# REZZ-Style_goggles.net
KiCad netlist of a schematic drawn in EAGLE
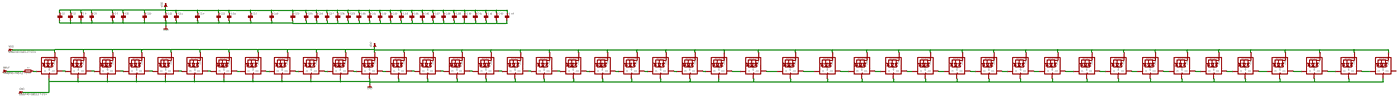
[diagram p0: schematic, sheet 1, overview]
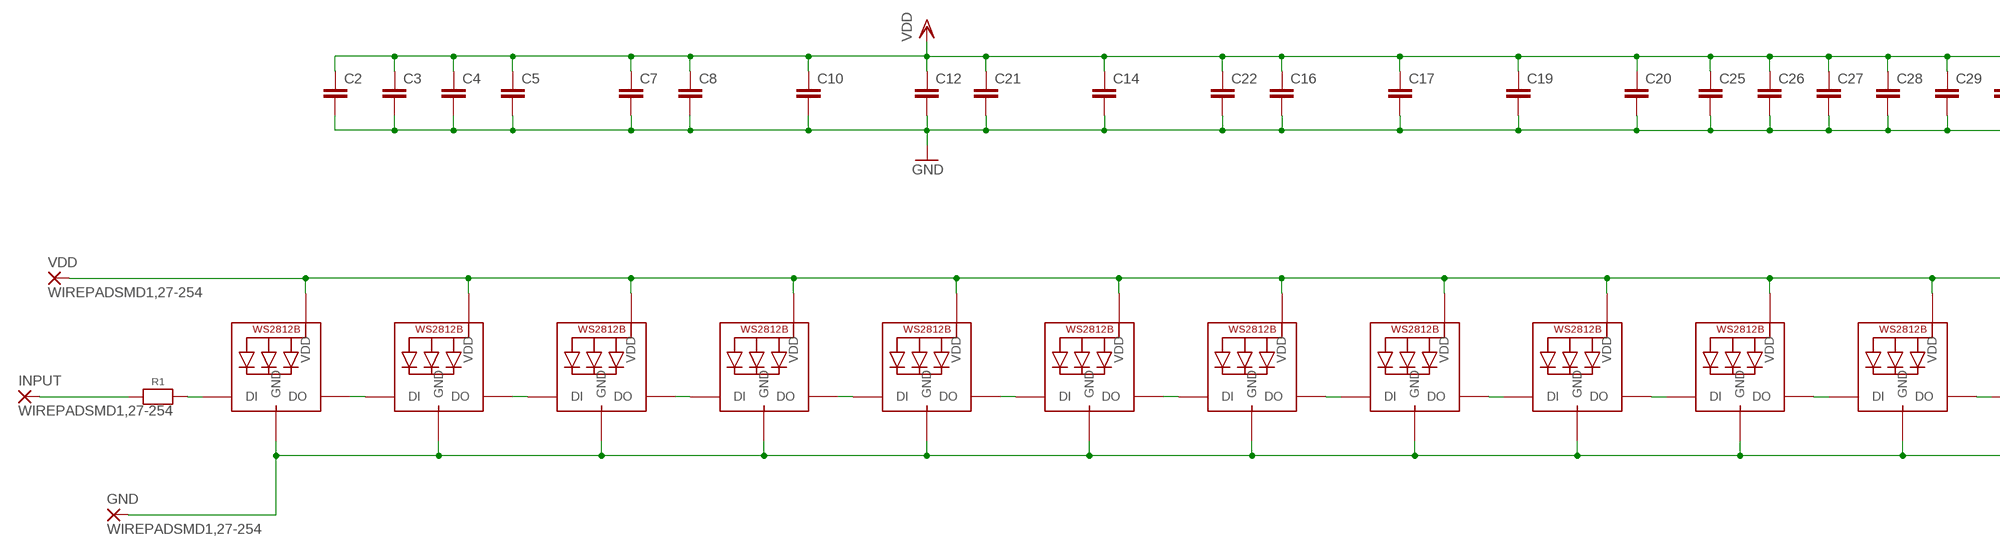
[diagram p1: schematic, sheet 1, part 1 of 4]
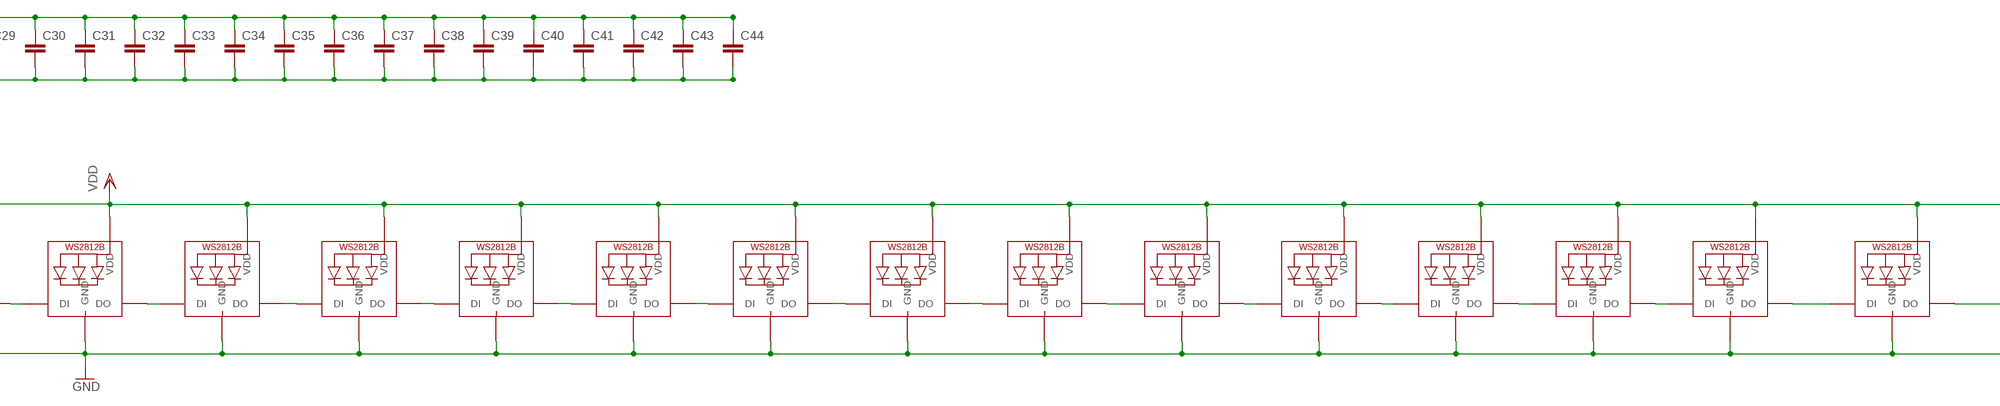
[diagram p2: schematic, sheet 1, part 2 of 4]
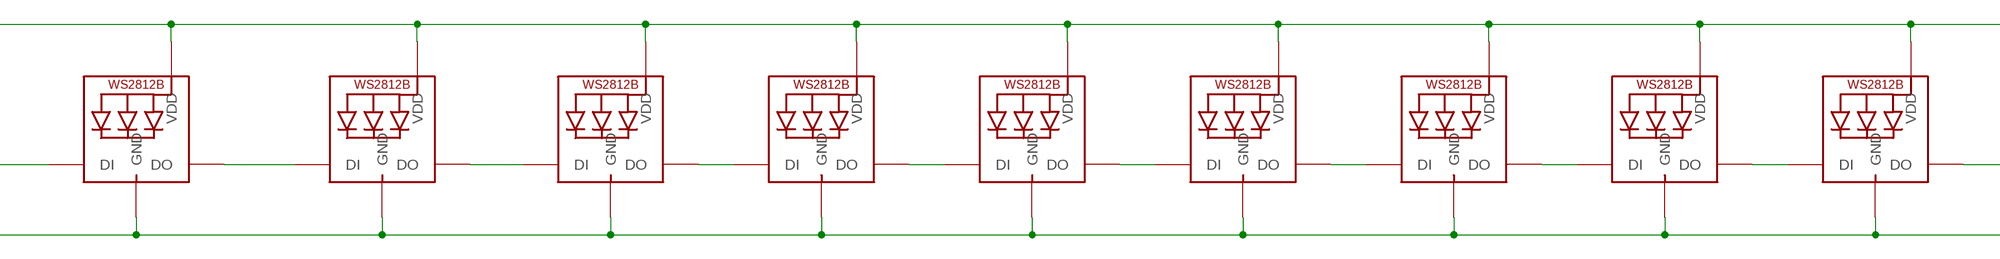
[diagram p3: schematic, sheet 1, part 3 of 4]
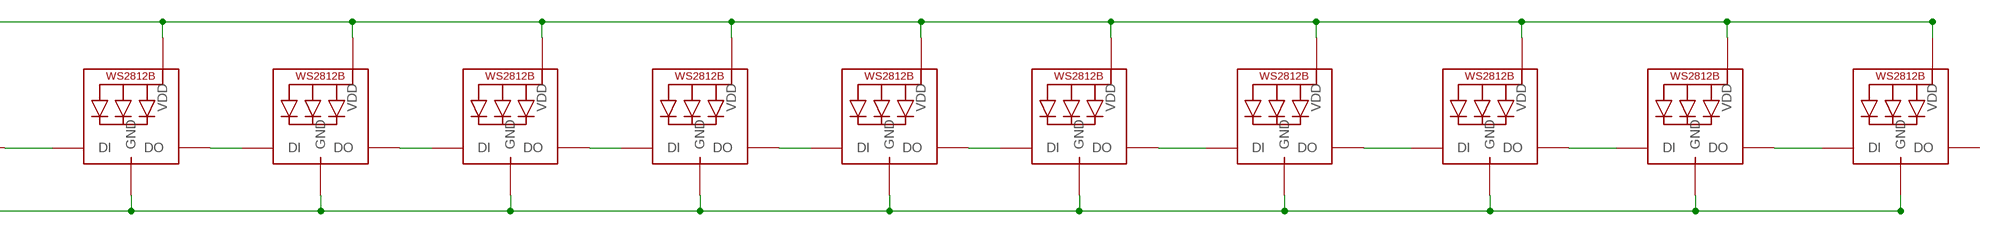
[diagram p4: schematic, sheet 1, part 4 of 4]

(export (version "E")
  (design (tool "Eeschema 10.0.6"))
  (components
    (comp (ref "C2")
      (value "C-EUC0603")
      (footprint "eagle-import:C0603")
      (libsource (lib "eagle-import") (part "C-EUC0603"))
    )
    (comp (ref "C3")
      (value "C-EUC0603")
      (footprint "eagle-import:C0603")
      (libsource (lib "eagle-import") (part "C-EUC0603"))
    )
    (comp (ref "C4")
      (value "C-EUC0603")
      (footprint "eagle-import:C0603")
      (libsource (lib "eagle-import") (part "C-EUC0603"))
    )
    (comp (ref "C5")
      (value "C-EUC0603")
      (footprint "eagle-import:C0603")
      (libsource (lib "eagle-import") (part "C-EUC0603"))
    )
    (comp (ref "C7")
      (value "C-EUC0603")
      (footprint "eagle-import:C0603")
      (libsource (lib "eagle-import") (part "C-EUC0603"))
    )
    (comp (ref "C8")
      (value "C-EUC0603")
      (footprint "eagle-import:C0603")
      (libsource (lib "eagle-import") (part "C-EUC0603"))
    )
    (comp (ref "C10")
      (value "C-EUC0603")
      (footprint "eagle-import:C0603")
      (libsource (lib "eagle-import") (part "C-EUC0603"))
    )
    (comp (ref "C12")
      (value "C-EUC0603")
      (footprint "eagle-import:C0603")
      (libsource (lib "eagle-import") (part "C-EUC0603"))
    )
    (comp (ref "C14")
      (value "C-EUC0603")
      (footprint "eagle-import:C0603")
      (libsource (lib "eagle-import") (part "C-EUC0603"))
    )
    (comp (ref "C16")
      (value "C-EUC0603")
      (footprint "eagle-import:C0603")
      (libsource (lib "eagle-import") (part "C-EUC0603"))
    )
    (comp (ref "C17")
      (value "C-EUC0603")
      (footprint "eagle-import:C0603")
      (libsource (lib "eagle-import") (part "C-EUC0603"))
    )
    (comp (ref "C19")
      (value "C-EUC0603")
      (footprint "eagle-import:C0603")
      (libsource (lib "eagle-import") (part "C-EUC0603"))
    )
    (comp (ref "C20")
      (value "C-EUC0603")
      (footprint "eagle-import:C0603")
      (libsource (lib "eagle-import") (part "C-EUC0603"))
    )
    (comp (ref "C21")
      (value "C-EUC0603")
      (footprint "eagle-import:C0603")
      (libsource (lib "eagle-import") (part "C-EUC0603"))
    )
    (comp (ref "C22")
      (value "C-EUC0603")
      (footprint "eagle-import:C0603")
      (libsource (lib "eagle-import") (part "C-EUC0603"))
    )
    (comp (ref "C25")
      (value "C-EUC0603")
      (footprint "eagle-import:C0603")
      (libsource (lib "eagle-import") (part "C-EUC0603"))
    )
    (comp (ref "C26")
      (value "C-EUC0603")
      (footprint "eagle-import:C0603")
      (libsource (lib "eagle-import") (part "C-EUC0603"))
    )
    (comp (ref "C27")
      (value "C-EUC0603")
      (footprint "eagle-import:C0603")
      (libsource (lib "eagle-import") (part "C-EUC0603"))
    )
    (comp (ref "C28")
      (value "C-EUC0603")
      (footprint "eagle-import:C0603")
      (libsource (lib "eagle-import") (part "C-EUC0603"))
    )
    (comp (ref "C29")
      (value "C-EUC0603")
      (footprint "eagle-import:C0603")
      (libsource (lib "eagle-import") (part "C-EUC0603"))
    )
    (comp (ref "C30")
      (value "C-EUC0603")
      (footprint "eagle-import:C0603")
      (libsource (lib "eagle-import") (part "C-EUC0603"))
    )
    (comp (ref "C31")
      (value "C-EUC0603")
      (footprint "eagle-import:C0603")
      (libsource (lib "eagle-import") (part "C-EUC0603"))
    )
    (comp (ref "C32")
      (value "C-EUC0603")
      (footprint "eagle-import:C0603")
      (libsource (lib "eagle-import") (part "C-EUC0603"))
    )
    (comp (ref "C33")
      (value "C-EUC0603")
      (footprint "eagle-import:C0603")
      (libsource (lib "eagle-import") (part "C-EUC0603"))
    )
    (comp (ref "C34")
      (value "C-EUC0603")
      (footprint "eagle-import:C0603")
      (libsource (lib "eagle-import") (part "C-EUC0603"))
    )
    (comp (ref "C35")
      (value "C-EUC0603")
      (footprint "eagle-import:C0603")
      (libsource (lib "eagle-import") (part "C-EUC0603"))
    )
    (comp (ref "C36")
      (value "C-EUC0603")
      (footprint "eagle-import:C0603")
      (libsource (lib "eagle-import") (part "C-EUC0603"))
    )
    (comp (ref "C37")
      (value "C-EUC0603")
      (footprint "eagle-import:C0603")
      (libsource (lib "eagle-import") (part "C-EUC0603"))
    )
    (comp (ref "C38")
      (value "C-EUC0603")
      (footprint "eagle-import:C0603")
      (libsource (lib "eagle-import") (part "C-EUC0603"))
    )
    (comp (ref "C39")
      (value "C-EUC0603")
      (footprint "eagle-import:C0603")
      (libsource (lib "eagle-import") (part "C-EUC0603"))
    )
    (comp (ref "C40")
      (value "C-EUC0603")
      (footprint "eagle-import:C0603")
      (libsource (lib "eagle-import") (part "C-EUC0603"))
    )
    (comp (ref "C41")
      (value "C-EUC0603")
      (footprint "eagle-import:C0603")
      (libsource (lib "eagle-import") (part "C-EUC0603"))
    )
    (comp (ref "C42")
      (value "C-EUC0603")
      (footprint "eagle-import:C0603")
      (libsource (lib "eagle-import") (part "C-EUC0603"))
    )
    (comp (ref "C43")
      (value "C-EUC0603")
      (footprint "eagle-import:C0603")
      (libsource (lib "eagle-import") (part "C-EUC0603"))
    )
    (comp (ref "C44")
      (value "C-EUC0603")
      (footprint "eagle-import:C0603")
      (libsource (lib "eagle-import") (part "C-EUC0603"))
    )
    (comp (ref "GND")
      (value "WIREPADSMD1,27-254")
      (footprint "eagle-import:SMD1,27-2,54")
      (libsource (lib "eagle-import") (part "WIREPADSMD1,27-254"))
    )
    (comp (ref "INPUT")
      (value "WIREPADSMD1,27-254")
      (footprint "eagle-import:SMD1,27-2,54")
      (libsource (lib "eagle-import") (part "WIREPADSMD1,27-254"))
    )
    (comp (ref "LED1")
      (value "WS2812B3535")
      (footprint "eagle-import:LED3535")
      (libsource (lib "eagle-import") (part "WS2812B3535"))
    )
    (comp (ref "LED2")
      (value "WS2812B3535")
      (footprint "eagle-import:LED3535")
      (libsource (lib "eagle-import") (part "WS2812B3535"))
    )
    (comp (ref "LED3")
      (value "WS2812B3535")
      (footprint "eagle-import:LED3535")
      (libsource (lib "eagle-import") (part "WS2812B3535"))
    )
    (comp (ref "LED4")
      (value "WS2812B3535")
      (footprint "eagle-import:LED3535")
      (libsource (lib "eagle-import") (part "WS2812B3535"))
    )
    (comp (ref "LED5")
      (value "WS2812B3535")
      (footprint "eagle-import:LED3535")
      (libsource (lib "eagle-import") (part "WS2812B3535"))
    )
    (comp (ref "LED6")
      (value "WS2812B3535")
      (footprint "eagle-import:LED3535")
      (libsource (lib "eagle-import") (part "WS2812B3535"))
    )
    (comp (ref "LED7")
      (value "WS2812B3535")
      (footprint "eagle-import:LED3535")
      (libsource (lib "eagle-import") (part "WS2812B3535"))
    )
    (comp (ref "LED8")
      (value "WS2812B3535")
      (footprint "eagle-import:LED3535")
      (libsource (lib "eagle-import") (part "WS2812B3535"))
    )
    (comp (ref "LED9")
      (value "WS2812B3535")
      (footprint "eagle-import:LED3535")
      (libsource (lib "eagle-import") (part "WS2812B3535"))
    )
    (comp (ref "LED10")
      (value "WS2812B3535")
      (footprint "eagle-import:LED3535")
      (libsource (lib "eagle-import") (part "WS2812B3535"))
    )
    (comp (ref "LED11")
      (value "WS2812B3535")
      (footprint "eagle-import:LED3535")
      (libsource (lib "eagle-import") (part "WS2812B3535"))
    )
    (comp (ref "LED12")
      (value "WS2812B3535")
      (footprint "eagle-import:LED3535")
      (libsource (lib "eagle-import") (part "WS2812B3535"))
    )
    (comp (ref "LED13")
      (value "WS2812B3535")
      (footprint "eagle-import:LED3535")
      (libsource (lib "eagle-import") (part "WS2812B3535"))
    )
    (comp (ref "LED14")
      (value "WS2812B3535")
      (footprint "eagle-import:LED3535")
      (libsource (lib "eagle-import") (part "WS2812B3535"))
    )
    (comp (ref "LED15")
      (value "WS2812B3535")
      (footprint "eagle-import:LED3535")
      (libsource (lib "eagle-import") (part "WS2812B3535"))
    )
    (comp (ref "LED16")
      (value "WS2812B3535")
      (footprint "eagle-import:LED3535")
      (libsource (lib "eagle-import") (part "WS2812B3535"))
    )
    (comp (ref "LED17")
      (value "WS2812B3535")
      (footprint "eagle-import:LED3535")
      (libsource (lib "eagle-import") (part "WS2812B3535"))
    )
    (comp (ref "LED18")
      (value "WS2812B3535")
      (footprint "eagle-import:LED3535")
      (libsource (lib "eagle-import") (part "WS2812B3535"))
    )
    (comp (ref "LED19")
      (value "WS2812B3535")
      (footprint "eagle-import:LED3535")
      (libsource (lib "eagle-import") (part "WS2812B3535"))
    )
    (comp (ref "LED20")
      (value "WS2812B3535")
      (footprint "eagle-import:LED3535")
      (libsource (lib "eagle-import") (part "WS2812B3535"))
    )
    (comp (ref "LED21")
      (value "WS2812B3535")
      (footprint "eagle-import:LED3535")
      (libsource (lib "eagle-import") (part "WS2812B3535"))
    )
    (comp (ref "LED22")
      (value "WS2812B3535")
      (footprint "eagle-import:LED3535")
      (libsource (lib "eagle-import") (part "WS2812B3535"))
    )
    (comp (ref "LED23")
      (value "WS2812B3535")
      (footprint "eagle-import:LED3535")
      (libsource (lib "eagle-import") (part "WS2812B3535"))
    )
    (comp (ref "LED24")
      (value "WS2812B3535")
      (footprint "eagle-import:LED3535")
      (libsource (lib "eagle-import") (part "WS2812B3535"))
    )
    (comp (ref "LED25")
      (value "WS2812B3535")
      (footprint "eagle-import:LED3535")
      (libsource (lib "eagle-import") (part "WS2812B3535"))
    )
    (comp (ref "LED26")
      (value "WS2812B3535")
      (footprint "eagle-import:LED3535")
      (libsource (lib "eagle-import") (part "WS2812B3535"))
    )
    (comp (ref "LED27")
      (value "WS2812B3535")
      (footprint "eagle-import:LED3535")
      (libsource (lib "eagle-import") (part "WS2812B3535"))
    )
    (comp (ref "LED28")
      (value "WS2812B3535")
      (footprint "eagle-import:LED3535")
      (libsource (lib "eagle-import") (part "WS2812B3535"))
    )
    (comp (ref "LED29")
      (value "WS2812B3535")
      (footprint "eagle-import:LED3535")
      (libsource (lib "eagle-import") (part "WS2812B3535"))
    )
    (comp (ref "LED30")
      (value "WS2812B3535")
      (footprint "eagle-import:LED3535")
      (libsource (lib "eagle-import") (part "WS2812B3535"))
    )
    (comp (ref "LED31")
      (value "WS2812B3535")
      (footprint "eagle-import:LED3535")
      (libsource (lib "eagle-import") (part "WS2812B3535"))
    )
    (comp (ref "LED32")
      (value "WS2812B3535")
      (footprint "eagle-import:LED3535")
      (libsource (lib "eagle-import") (part "WS2812B3535"))
    )
    (comp (ref "LED33")
      (value "WS2812B3535")
      (footprint "eagle-import:LED3535")
      (libsource (lib "eagle-import") (part "WS2812B3535"))
    )
    (comp (ref "LED34")
      (value "WS2812B3535")
      (footprint "eagle-import:LED3535")
      (libsource (lib "eagle-import") (part "WS2812B3535"))
    )
    (comp (ref "LED35")
      (value "WS2812B3535")
      (footprint "eagle-import:LED3535")
      (libsource (lib "eagle-import") (part "WS2812B3535"))
    )
    (comp (ref "LED36")
      (value "WS2812B3535")
      (footprint "eagle-import:LED3535")
      (libsource (lib "eagle-import") (part "WS2812B3535"))
    )
    (comp (ref "LED37")
      (value "WS2812B3535")
      (footprint "eagle-import:LED3535")
      (libsource (lib "eagle-import") (part "WS2812B3535"))
    )
    (comp (ref "LED38")
      (value "WS2812B3535")
      (footprint "eagle-import:LED3535")
      (libsource (lib "eagle-import") (part "WS2812B3535"))
    )
    (comp (ref "LED39")
      (value "WS2812B3535")
      (footprint "eagle-import:LED3535")
      (libsource (lib "eagle-import") (part "WS2812B3535"))
    )
    (comp (ref "LED40")
      (value "WS2812B3535")
      (footprint "eagle-import:LED3535")
      (libsource (lib "eagle-import") (part "WS2812B3535"))
    )
    (comp (ref "LED41")
      (value "WS2812B3535")
      (footprint "eagle-import:LED3535")
      (libsource (lib "eagle-import") (part "WS2812B3535"))
    )
    (comp (ref "LED42")
      (value "WS2812B3535")
      (footprint "eagle-import:LED3535")
      (libsource (lib "eagle-import") (part "WS2812B3535"))
    )
    (comp (ref "LED43")
      (value "WS2812B3535")
      (footprint "eagle-import:LED3535")
      (libsource (lib "eagle-import") (part "WS2812B3535"))
    )
    (comp (ref "LED44")
      (value "WS2812B3535")
      (footprint "eagle-import:LED3535")
      (libsource (lib "eagle-import") (part "WS2812B3535"))
    )
    (comp (ref "R1")
      (value "RESISTOR_0603_NOOUT")
      (footprint "eagle-import:0603-NO")
      (libsource (lib "eagle-import") (part "RESISTOR_0603_NOOUT"))
    )
    (comp (ref "VDD")
      (value "WIREPADSMD1,27-254")
      (footprint "eagle-import:SMD1,27-2,54")
      (libsource (lib "eagle-import") (part "WIREPADSMD1,27-254"))
    )
  )
  (nets
    (net (code "1") (name "GND") (class "Default")
      (node (ref "C10") (pin "2") (pinfunction "2_2") (pintype "passive"))
      (node (ref "C12") (pin "2") (pinfunction "2_2") (pintype "passive"))
      (node (ref "C14") (pin "2") (pinfunction "2_2") (pintype "passive"))
      (node (ref "C16") (pin "2") (pinfunction "2_2") (pintype "passive"))
      (node (ref "C17") (pin "2") (pinfunction "2_2") (pintype "passive"))
      (node (ref "C19") (pin "2") (pinfunction "2_2") (pintype "passive"))
      (node (ref "C2") (pin "2") (pinfunction "2_2") (pintype "passive"))
      (node (ref "C20") (pin "2") (pinfunction "2_2") (pintype "passive"))
      (node (ref "C21") (pin "2") (pinfunction "2_2") (pintype "passive"))
      (node (ref "C22") (pin "2") (pinfunction "2_2") (pintype "passive"))
      (node (ref "C25") (pin "2") (pinfunction "2_2") (pintype "passive"))
      (node (ref "C26") (pin "2") (pinfunction "2_2") (pintype "passive"))
      (node (ref "C27") (pin "2") (pinfunction "2_2") (pintype "passive"))
      (node (ref "C28") (pin "2") (pinfunction "2_2") (pintype "passive"))
      (node (ref "C29") (pin "2") (pinfunction "2_2") (pintype "passive"))
      (node (ref "C3") (pin "2") (pinfunction "2_2") (pintype "passive"))
      (node (ref "C30") (pin "2") (pinfunction "2_2") (pintype "passive"))
      (node (ref "C31") (pin "2") (pinfunction "2_2") (pintype "passive"))
      (node (ref "C32") (pin "2") (pinfunction "2_2") (pintype "passive"))
      (node (ref "C33") (pin "2") (pinfunction "2_2") (pintype "passive"))
      (node (ref "C34") (pin "2") (pinfunction "2_2") (pintype "passive"))
      (node (ref "C35") (pin "2") (pinfunction "2_2") (pintype "passive"))
      (node (ref "C36") (pin "2") (pinfunction "2_2") (pintype "passive"))
      (node (ref "C37") (pin "2") (pinfunction "2_2") (pintype "passive"))
      (node (ref "C38") (pin "2") (pinfunction "2_2") (pintype "passive"))
      (node (ref "C39") (pin "2") (pinfunction "2_2") (pintype "passive"))
      (node (ref "C4") (pin "2") (pinfunction "2_2") (pintype "passive"))
      (node (ref "C40") (pin "2") (pinfunction "2_2") (pintype "passive"))
      (node (ref "C41") (pin "2") (pinfunction "2_2") (pintype "passive"))
      (node (ref "C42") (pin "2") (pinfunction "2_2") (pintype "passive"))
      (node (ref "C43") (pin "2") (pinfunction "2_2") (pintype "passive"))
      (node (ref "C44") (pin "2") (pinfunction "2_2") (pintype "passive"))
      (node (ref "C5") (pin "2") (pinfunction "2_2") (pintype "passive"))
      (node (ref "C7") (pin "2") (pinfunction "2_2") (pintype "passive"))
      (node (ref "C8") (pin "2") (pinfunction "2_2") (pintype "passive"))
      (node (ref "GND") (pin "1") (pinfunction "P_1") (pintype "passive"))
      (node (ref "LED1") (pin "4") (pinfunction "GND_4") (pintype "power_in"))
      (node (ref "LED10") (pin "4") (pinfunction "GND_4") (pintype "power_in"))
      (node (ref "LED11") (pin "4") (pinfunction "GND_4") (pintype "power_in"))
      (node (ref "LED12") (pin "4") (pinfunction "GND_4") (pintype "power_in"))
      (node (ref "LED13") (pin "4") (pinfunction "GND_4") (pintype "power_in"))
      (node (ref "LED14") (pin "4") (pinfunction "GND_4") (pintype "power_in"))
      (node (ref "LED15") (pin "4") (pinfunction "GND_4") (pintype "power_in"))
      (node (ref "LED16") (pin "4") (pinfunction "GND_4") (pintype "power_in"))
      (node (ref "LED17") (pin "4") (pinfunction "GND_4") (pintype "power_in"))
      (node (ref "LED18") (pin "4") (pinfunction "GND_4") (pintype "power_in"))
      (node (ref "LED19") (pin "4") (pinfunction "GND_4") (pintype "power_in"))
      (node (ref "LED2") (pin "4") (pinfunction "GND_4") (pintype "power_in"))
      (node (ref "LED20") (pin "4") (pinfunction "GND_4") (pintype "power_in"))
      (node (ref "LED21") (pin "4") (pinfunction "GND_4") (pintype "power_in"))
      (node (ref "LED22") (pin "4") (pinfunction "GND_4") (pintype "power_in"))
      (node (ref "LED23") (pin "4") (pinfunction "GND_4") (pintype "power_in"))
      (node (ref "LED24") (pin "4") (pinfunction "GND_4") (pintype "power_in"))
      (node (ref "LED25") (pin "4") (pinfunction "GND_4") (pintype "power_in"))
      (node (ref "LED26") (pin "4") (pinfunction "GND_4") (pintype "power_in"))
      (node (ref "LED27") (pin "4") (pinfunction "GND_4") (pintype "power_in"))
      (node (ref "LED28") (pin "4") (pinfunction "GND_4") (pintype "power_in"))
      (node (ref "LED29") (pin "4") (pinfunction "GND_4") (pintype "power_in"))
      (node (ref "LED3") (pin "4") (pinfunction "GND_4") (pintype "power_in"))
      (node (ref "LED30") (pin "4") (pinfunction "GND_4") (pintype "power_in"))
      (node (ref "LED31") (pin "4") (pinfunction "GND_4") (pintype "power_in"))
      (node (ref "LED32") (pin "4") (pinfunction "GND_4") (pintype "power_in"))
      (node (ref "LED33") (pin "4") (pinfunction "GND_4") (pintype "power_in"))
      (node (ref "LED34") (pin "4") (pinfunction "GND_4") (pintype "power_in"))
      (node (ref "LED35") (pin "4") (pinfunction "GND_4") (pintype "power_in"))
      (node (ref "LED36") (pin "4") (pinfunction "GND_4") (pintype "power_in"))
      (node (ref "LED37") (pin "4") (pinfunction "GND_4") (pintype "power_in"))
      (node (ref "LED38") (pin "4") (pinfunction "GND_4") (pintype "power_in"))
      (node (ref "LED39") (pin "4") (pinfunction "GND_4") (pintype "power_in"))
      (node (ref "LED4") (pin "4") (pinfunction "GND_4") (pintype "power_in"))
      (node (ref "LED40") (pin "4") (pinfunction "GND_4") (pintype "power_in"))
      (node (ref "LED41") (pin "4") (pinfunction "GND_4") (pintype "power_in"))
      (node (ref "LED42") (pin "4") (pinfunction "GND_4") (pintype "power_in"))
      (node (ref "LED43") (pin "4") (pinfunction "GND_4") (pintype "power_in"))
      (node (ref "LED44") (pin "4") (pinfunction "GND_4") (pintype "power_in"))
      (node (ref "LED5") (pin "4") (pinfunction "GND_4") (pintype "power_in"))
      (node (ref "LED6") (pin "4") (pinfunction "GND_4") (pintype "power_in"))
      (node (ref "LED7") (pin "4") (pinfunction "GND_4") (pintype "power_in"))
      (node (ref "LED8") (pin "4") (pinfunction "GND_4") (pintype "power_in"))
      (node (ref "LED9") (pin "4") (pinfunction "GND_4") (pintype "power_in"))
    )
    (net (code "2") (name "Net-(INPUT-P)") (class "Default")
      (node (ref "INPUT") (pin "1") (pinfunction "P_1") (pintype "passive"))
      (node (ref "R1") (pin "1") (pinfunction "1_1") (pintype "passive"))
    )
    (net (code "3") (name "Net-(LED1-DI)") (class "Default")
      (node (ref "LED1") (pin "1") (pinfunction "DI_1") (pintype "input"))
      (node (ref "R1") (pin "2") (pinfunction "2_2") (pintype "passive"))
    )
    (net (code "4") (name "Net-(LED1-DO)") (class "Default")
      (node (ref "LED1") (pin "3") (pinfunction "DO_3") (pintype "output"))
      (node (ref "LED2") (pin "1") (pinfunction "DI_1") (pintype "input"))
    )
    (net (code "5") (name "Net-(LED2-DO)") (class "Default")
      (node (ref "LED2") (pin "3") (pinfunction "DO_3") (pintype "output"))
      (node (ref "LED3") (pin "1") (pinfunction "DI_1") (pintype "input"))
    )
    (net (code "6") (name "Net-(LED3-DO)") (class "Default")
      (node (ref "LED3") (pin "3") (pinfunction "DO_3") (pintype "output"))
      (node (ref "LED4") (pin "1") (pinfunction "DI_1") (pintype "input"))
    )
    (net (code "7") (name "Net-(LED4-DO)") (class "Default")
      (node (ref "LED4") (pin "3") (pinfunction "DO_3") (pintype "output"))
      (node (ref "LED5") (pin "1") (pinfunction "DI_1") (pintype "input"))
    )
    (net (code "8") (name "Net-(LED5-DO)") (class "Default")
      (node (ref "LED5") (pin "3") (pinfunction "DO_3") (pintype "output"))
      (node (ref "LED6") (pin "1") (pinfunction "DI_1") (pintype "input"))
    )
    (net (code "9") (name "Net-(LED6-DO)") (class "Default")
      (node (ref "LED6") (pin "3") (pinfunction "DO_3") (pintype "output"))
      (node (ref "LED7") (pin "1") (pinfunction "DI_1") (pintype "input"))
    )
    (net (code "10") (name "Net-(LED7-DO)") (class "Default")
      (node (ref "LED7") (pin "3") (pinfunction "DO_3") (pintype "output"))
      (node (ref "LED8") (pin "1") (pinfunction "DI_1") (pintype "input"))
    )
    (net (code "11") (name "Net-(LED8-DO)") (class "Default")
      (node (ref "LED8") (pin "3") (pinfunction "DO_3") (pintype "output"))
      (node (ref "LED9") (pin "1") (pinfunction "DI_1") (pintype "input"))
    )
    (net (code "12") (name "Net-(LED10-DI)") (class "Default")
      (node (ref "LED10") (pin "1") (pinfunction "DI_1") (pintype "input"))
      (node (ref "LED9") (pin "3") (pinfunction "DO_3") (pintype "output"))
    )
    (net (code "13") (name "Net-(LED10-DO)") (class "Default")
      (node (ref "LED10") (pin "3") (pinfunction "DO_3") (pintype "output"))
      (node (ref "LED11") (pin "1") (pinfunction "DI_1") (pintype "input"))
    )
    (net (code "14") (name "Net-(LED11-DO)") (class "Default")
      (node (ref "LED11") (pin "3") (pinfunction "DO_3") (pintype "output"))
      (node (ref "LED12") (pin "1") (pinfunction "DI_1") (pintype "input"))
    )
    (net (code "15") (name "Net-(LED12-DO)") (class "Default")
      (node (ref "LED12") (pin "3") (pinfunction "DO_3") (pintype "output"))
      (node (ref "LED13") (pin "1") (pinfunction "DI_1") (pintype "input"))
    )
    (net (code "16") (name "Net-(LED13-DO)") (class "Default")
      (node (ref "LED13") (pin "3") (pinfunction "DO_3") (pintype "output"))
      (node (ref "LED14") (pin "1") (pinfunction "DI_1") (pintype "input"))
    )
    (net (code "17") (name "Net-(LED14-DO)") (class "Default")
      (node (ref "LED14") (pin "3") (pinfunction "DO_3") (pintype "output"))
      (node (ref "LED15") (pin "1") (pinfunction "DI_1") (pintype "input"))
    )
    (net (code "18") (name "Net-(LED15-DO)") (class "Default")
      (node (ref "LED15") (pin "3") (pinfunction "DO_3") (pintype "output"))
      (node (ref "LED16") (pin "1") (pinfunction "DI_1") (pintype "input"))
    )
    (net (code "19") (name "Net-(LED16-DO)") (class "Default")
      (node (ref "LED16") (pin "3") (pinfunction "DO_3") (pintype "output"))
      (node (ref "LED17") (pin "1") (pinfunction "DI_1") (pintype "input"))
    )
    (net (code "20") (name "Net-(LED17-DO)") (class "Default")
      (node (ref "LED17") (pin "3") (pinfunction "DO_3") (pintype "output"))
      (node (ref "LED18") (pin "1") (pinfunction "DI_1") (pintype "input"))
    )
    (net (code "21") (name "Net-(LED18-DO)") (class "Default")
      (node (ref "LED18") (pin "3") (pinfunction "DO_3") (pintype "output"))
      (node (ref "LED19") (pin "1") (pinfunction "DI_1") (pintype "input"))
    )
    (net (code "22") (name "Net-(LED19-DO)") (class "Default")
      (node (ref "LED19") (pin "3") (pinfunction "DO_3") (pintype "output"))
      (node (ref "LED20") (pin "1") (pinfunction "DI_1") (pintype "input"))
    )
    (net (code "23") (name "Net-(LED20-DO)") (class "Default")
      (node (ref "LED20") (pin "3") (pinfunction "DO_3") (pintype "output"))
      (node (ref "LED21") (pin "1") (pinfunction "DI_1") (pintype "input"))
    )
    (net (code "24") (name "Net-(LED21-DO)") (class "Default")
      (node (ref "LED21") (pin "3") (pinfunction "DO_3") (pintype "output"))
      (node (ref "LED22") (pin "1") (pinfunction "DI_1") (pintype "input"))
    )
    (net (code "25") (name "Net-(LED22-DO)") (class "Default")
      (node (ref "LED22") (pin "3") (pinfunction "DO_3") (pintype "output"))
      (node (ref "LED23") (pin "1") (pinfunction "DI_1") (pintype "input"))
    )
    (net (code "26") (name "Net-(LED23-DO)") (class "Default")
      (node (ref "LED23") (pin "3") (pinfunction "DO_3") (pintype "output"))
      (node (ref "LED24") (pin "1") (pinfunction "DI_1") (pintype "input"))
    )
    (net (code "27") (name "Net-(LED24-DO)") (class "Default")
      (node (ref "LED24") (pin "3") (pinfunction "DO_3") (pintype "output"))
      (node (ref "LED25") (pin "1") (pinfunction "DI_1") (pintype "input"))
    )
    (net (code "28") (name "Net-(LED25-DO)") (class "Default")
      (node (ref "LED25") (pin "3") (pinfunction "DO_3") (pintype "output"))
      (node (ref "LED26") (pin "1") (pinfunction "DI_1") (pintype "input"))
    )
    (net (code "29") (name "Net-(LED26-DO)") (class "Default")
      (node (ref "LED26") (pin "3") (pinfunction "DO_3") (pintype "output"))
      (node (ref "LED27") (pin "1") (pinfunction "DI_1") (pintype "input"))
    )
    (net (code "30") (name "Net-(LED27-DO)") (class "Default")
      (node (ref "LED27") (pin "3") (pinfunction "DO_3") (pintype "output"))
      (node (ref "LED28") (pin "1") (pinfunction "DI_1") (pintype "input"))
    )
    (net (code "31") (name "Net-(LED28-DO)") (class "Default")
      (node (ref "LED28") (pin "3") (pinfunction "DO_3") (pintype "output"))
      (node (ref "LED29") (pin "1") (pinfunction "DI_1") (pintype "input"))
    )
    (net (code "32") (name "Net-(LED29-DO)") (class "Default")
      (node (ref "LED29") (pin "3") (pinfunction "DO_3") (pintype "output"))
      (node (ref "LED30") (pin "1") (pinfunction "DI_1") (pintype "input"))
    )
    (net (code "33") (name "Net-(LED30-DO)") (class "Default")
      (node (ref "LED30") (pin "3") (pinfunction "DO_3") (pintype "output"))
      (node (ref "LED31") (pin "1") (pinfunction "DI_1") (pintype "input"))
    )
    (net (code "34") (name "Net-(LED31-DO)") (class "Default")
      (node (ref "LED31") (pin "3") (pinfunction "DO_3") (pintype "output"))
      (node (ref "LED32") (pin "1") (pinfunction "DI_1") (pintype "input"))
    )
    (net (code "35") (name "Net-(LED32-DO)") (class "Default")
      (node (ref "LED32") (pin "3") (pinfunction "DO_3") (pintype "output"))
      (node (ref "LED33") (pin "1") (pinfunction "DI_1") (pintype "input"))
    )
    (net (code "36") (name "Net-(LED33-DO)") (class "Default")
      (node (ref "LED33") (pin "3") (pinfunction "DO_3") (pintype "output"))
      (node (ref "LED34") (pin "1") (pinfunction "DI_1") (pintype "input"))
    )
    (net (code "37") (name "Net-(LED34-DO)") (class "Default")
      (node (ref "LED34") (pin "3") (pinfunction "DO_3") (pintype "output"))
      (node (ref "LED35") (pin "1") (pinfunction "DI_1") (pintype "input"))
    )
    (net (code "38") (name "Net-(LED35-DO)") (class "Default")
      (node (ref "LED35") (pin "3") (pinfunction "DO_3") (pintype "output"))
      (node (ref "LED36") (pin "1") (pinfunction "DI_1") (pintype "input"))
    )
    (net (code "39") (name "Net-(LED36-DO)") (class "Default")
      (node (ref "LED36") (pin "3") (pinfunction "DO_3") (pintype "output"))
      (node (ref "LED37") (pin "1") (pinfunction "DI_1") (pintype "input"))
    )
    (net (code "40") (name "Net-(LED37-DO)") (class "Default")
      (node (ref "LED37") (pin "3") (pinfunction "DO_3") (pintype "output"))
      (node (ref "LED38") (pin "1") (pinfunction "DI_1") (pintype "input"))
    )
    (net (code "41") (name "Net-(LED38-DO)") (class "Default")
      (node (ref "LED38") (pin "3") (pinfunction "DO_3") (pintype "output"))
      (node (ref "LED39") (pin "1") (pinfunction "DI_1") (pintype "input"))
    )
    (net (code "42") (name "Net-(LED39-DO)") (class "Default")
      (node (ref "LED39") (pin "3") (pinfunction "DO_3") (pintype "output"))
      (node (ref "LED40") (pin "1") (pinfunction "DI_1") (pintype "input"))
    )
    (net (code "43") (name "Net-(LED40-DO)") (class "Default")
      (node (ref "LED40") (pin "3") (pinfunction "DO_3") (pintype "output"))
      (node (ref "LED41") (pin "1") (pinfunction "DI_1") (pintype "input"))
    )
    (net (code "44") (name "Net-(LED41-DO)") (class "Default")
      (node (ref "LED41") (pin "3") (pinfunction "DO_3") (pintype "output"))
      (node (ref "LED42") (pin "1") (pinfunction "DI_1") (pintype "input"))
    )
    (net (code "45") (name "Net-(LED42-DO)") (class "Default")
      (node (ref "LED42") (pin "3") (pinfunction "DO_3") (pintype "output"))
      (node (ref "LED43") (pin "1") (pinfunction "DI_1") (pintype "input"))
    )
    (net (code "46") (name "Net-(LED43-DO)") (class "Default")
      (node (ref "LED43") (pin "3") (pinfunction "DO_3") (pintype "output"))
      (node (ref "LED44") (pin "1") (pinfunction "DI_1") (pintype "input"))
    )
    (net (code "47") (name "VDD") (class "Default")
      (node (ref "C10") (pin "1") (pinfunction "1_1") (pintype "passive"))
      (node (ref "C12") (pin "1") (pinfunction "1_1") (pintype "passive"))
      (node (ref "C14") (pin "1") (pinfunction "1_1") (pintype "passive"))
      (node (ref "C16") (pin "1") (pinfunction "1_1") (pintype "passive"))
      (node (ref "C17") (pin "1") (pinfunction "1_1") (pintype "passive"))
      (node (ref "C19") (pin "1") (pinfunction "1_1") (pintype "passive"))
      (node (ref "C2") (pin "1") (pinfunction "1_1") (pintype "passive"))
      (node (ref "C20") (pin "1") (pinfunction "1_1") (pintype "passive"))
      (node (ref "C21") (pin "1") (pinfunction "1_1") (pintype "passive"))
      (node (ref "C22") (pin "1") (pinfunction "1_1") (pintype "passive"))
      (node (ref "C25") (pin "1") (pinfunction "1_1") (pintype "passive"))
      (node (ref "C26") (pin "1") (pinfunction "1_1") (pintype "passive"))
      (node (ref "C27") (pin "1") (pinfunction "1_1") (pintype "passive"))
      (node (ref "C28") (pin "1") (pinfunction "1_1") (pintype "passive"))
      (node (ref "C29") (pin "1") (pinfunction "1_1") (pintype "passive"))
      (node (ref "C3") (pin "1") (pinfunction "1_1") (pintype "passive"))
      (node (ref "C30") (pin "1") (pinfunction "1_1") (pintype "passive"))
      (node (ref "C31") (pin "1") (pinfunction "1_1") (pintype "passive"))
      (node (ref "C32") (pin "1") (pinfunction "1_1") (pintype "passive"))
      (node (ref "C33") (pin "1") (pinfunction "1_1") (pintype "passive"))
      (node (ref "C34") (pin "1") (pinfunction "1_1") (pintype "passive"))
      (node (ref "C35") (pin "1") (pinfunction "1_1") (pintype "passive"))
      (node (ref "C36") (pin "1") (pinfunction "1_1") (pintype "passive"))
      (node (ref "C37") (pin "1") (pinfunction "1_1") (pintype "passive"))
      (node (ref "C38") (pin "1") (pinfunction "1_1") (pintype "passive"))
      (node (ref "C39") (pin "1") (pinfunction "1_1") (pintype "passive"))
      (node (ref "C4") (pin "1") (pinfunction "1_1") (pintype "passive"))
      (node (ref "C40") (pin "1") (pinfunction "1_1") (pintype "passive"))
      (node (ref "C41") (pin "1") (pinfunction "1_1") (pintype "passive"))
      (node (ref "C42") (pin "1") (pinfunction "1_1") (pintype "passive"))
      (node (ref "C43") (pin "1") (pinfunction "1_1") (pintype "passive"))
      (node (ref "C44") (pin "1") (pinfunction "1_1") (pintype "passive"))
      (node (ref "C5") (pin "1") (pinfunction "1_1") (pintype "passive"))
      (node (ref "C7") (pin "1") (pinfunction "1_1") (pintype "passive"))
      (node (ref "C8") (pin "1") (pinfunction "1_1") (pintype "passive"))
      (node (ref "LED1") (pin "2") (pinfunction "VDD_2") (pintype "power_in"))
      (node (ref "LED10") (pin "2") (pinfunction "VDD_2") (pintype "power_in"))
      (node (ref "LED11") (pin "2") (pinfunction "VDD_2") (pintype "power_in"))
      (node (ref "LED12") (pin "2") (pinfunction "VDD_2") (pintype "power_in"))
      (node (ref "LED13") (pin "2") (pinfunction "VDD_2") (pintype "power_in"))
      (node (ref "LED14") (pin "2") (pinfunction "VDD_2") (pintype "power_in"))
      (node (ref "LED15") (pin "2") (pinfunction "VDD_2") (pintype "power_in"))
      (node (ref "LED16") (pin "2") (pinfunction "VDD_2") (pintype "power_in"))
      (node (ref "LED17") (pin "2") (pinfunction "VDD_2") (pintype "power_in"))
      (node (ref "LED18") (pin "2") (pinfunction "VDD_2") (pintype "power_in"))
      (node (ref "LED19") (pin "2") (pinfunction "VDD_2") (pintype "power_in"))
      (node (ref "LED2") (pin "2") (pinfunction "VDD_2") (pintype "power_in"))
      (node (ref "LED20") (pin "2") (pinfunction "VDD_2") (pintype "power_in"))
      (node (ref "LED21") (pin "2") (pinfunction "VDD_2") (pintype "power_in"))
      (node (ref "LED22") (pin "2") (pinfunction "VDD_2") (pintype "power_in"))
      (node (ref "LED23") (pin "2") (pinfunction "VDD_2") (pintype "power_in"))
      (node (ref "LED24") (pin "2") (pinfunction "VDD_2") (pintype "power_in"))
      (node (ref "LED25") (pin "2") (pinfunction "VDD_2") (pintype "power_in"))
      (node (ref "LED26") (pin "2") (pinfunction "VDD_2") (pintype "power_in"))
      (node (ref "LED27") (pin "2") (pinfunction "VDD_2") (pintype "power_in"))
      (node (ref "LED28") (pin "2") (pinfunction "VDD_2") (pintype "power_in"))
      (node (ref "LED29") (pin "2") (pinfunction "VDD_2") (pintype "power_in"))
      (node (ref "LED3") (pin "2") (pinfunction "VDD_2") (pintype "power_in"))
      (node (ref "LED30") (pin "2") (pinfunction "VDD_2") (pintype "power_in"))
      (node (ref "LED31") (pin "2") (pinfunction "VDD_2") (pintype "power_in"))
      (node (ref "LED32") (pin "2") (pinfunction "VDD_2") (pintype "power_in"))
      (node (ref "LED33") (pin "2") (pinfunction "VDD_2") (pintype "power_in"))
      (node (ref "LED34") (pin "2") (pinfunction "VDD_2") (pintype "power_in"))
      (node (ref "LED35") (pin "2") (pinfunction "VDD_2") (pintype "power_in"))
      (node (ref "LED36") (pin "2") (pinfunction "VDD_2") (pintype "power_in"))
      (node (ref "LED37") (pin "2") (pinfunction "VDD_2") (pintype "power_in"))
      (node (ref "LED38") (pin "2") (pinfunction "VDD_2") (pintype "power_in"))
      (node (ref "LED39") (pin "2") (pinfunction "VDD_2") (pintype "power_in"))
      (node (ref "LED4") (pin "2") (pinfunction "VDD_2") (pintype "power_in"))
      (node (ref "LED40") (pin "2") (pinfunction "VDD_2") (pintype "power_in"))
      (node (ref "LED41") (pin "2") (pinfunction "VDD_2") (pintype "power_in"))
      (node (ref "LED42") (pin "2") (pinfunction "VDD_2") (pintype "power_in"))
      (node (ref "LED43") (pin "2") (pinfunction "VDD_2") (pintype "power_in"))
      (node (ref "LED44") (pin "2") (pinfunction "VDD_2") (pintype "power_in"))
      (node (ref "LED5") (pin "2") (pinfunction "VDD_2") (pintype "power_in"))
      (node (ref "LED6") (pin "2") (pinfunction "VDD_2") (pintype "power_in"))
      (node (ref "LED7") (pin "2") (pinfunction "VDD_2") (pintype "power_in"))
      (node (ref "LED8") (pin "2") (pinfunction "VDD_2") (pintype "power_in"))
      (node (ref "LED9") (pin "2") (pinfunction "VDD_2") (pintype "power_in"))
      (node (ref "VDD") (pin "1") (pinfunction "P_1") (pintype "passive"))
    )
    (net (code "48") (name "unconnected-(LED44-DO-Pad3)") (class "Default")
      (node (ref "LED44") (pin "3") (pinfunction "DO_3") (pintype "output"))
    )
  )
)
